# ELC102_-_Old_Circuits.net
KiCad netlist of a schematic drawn in Altium Designer
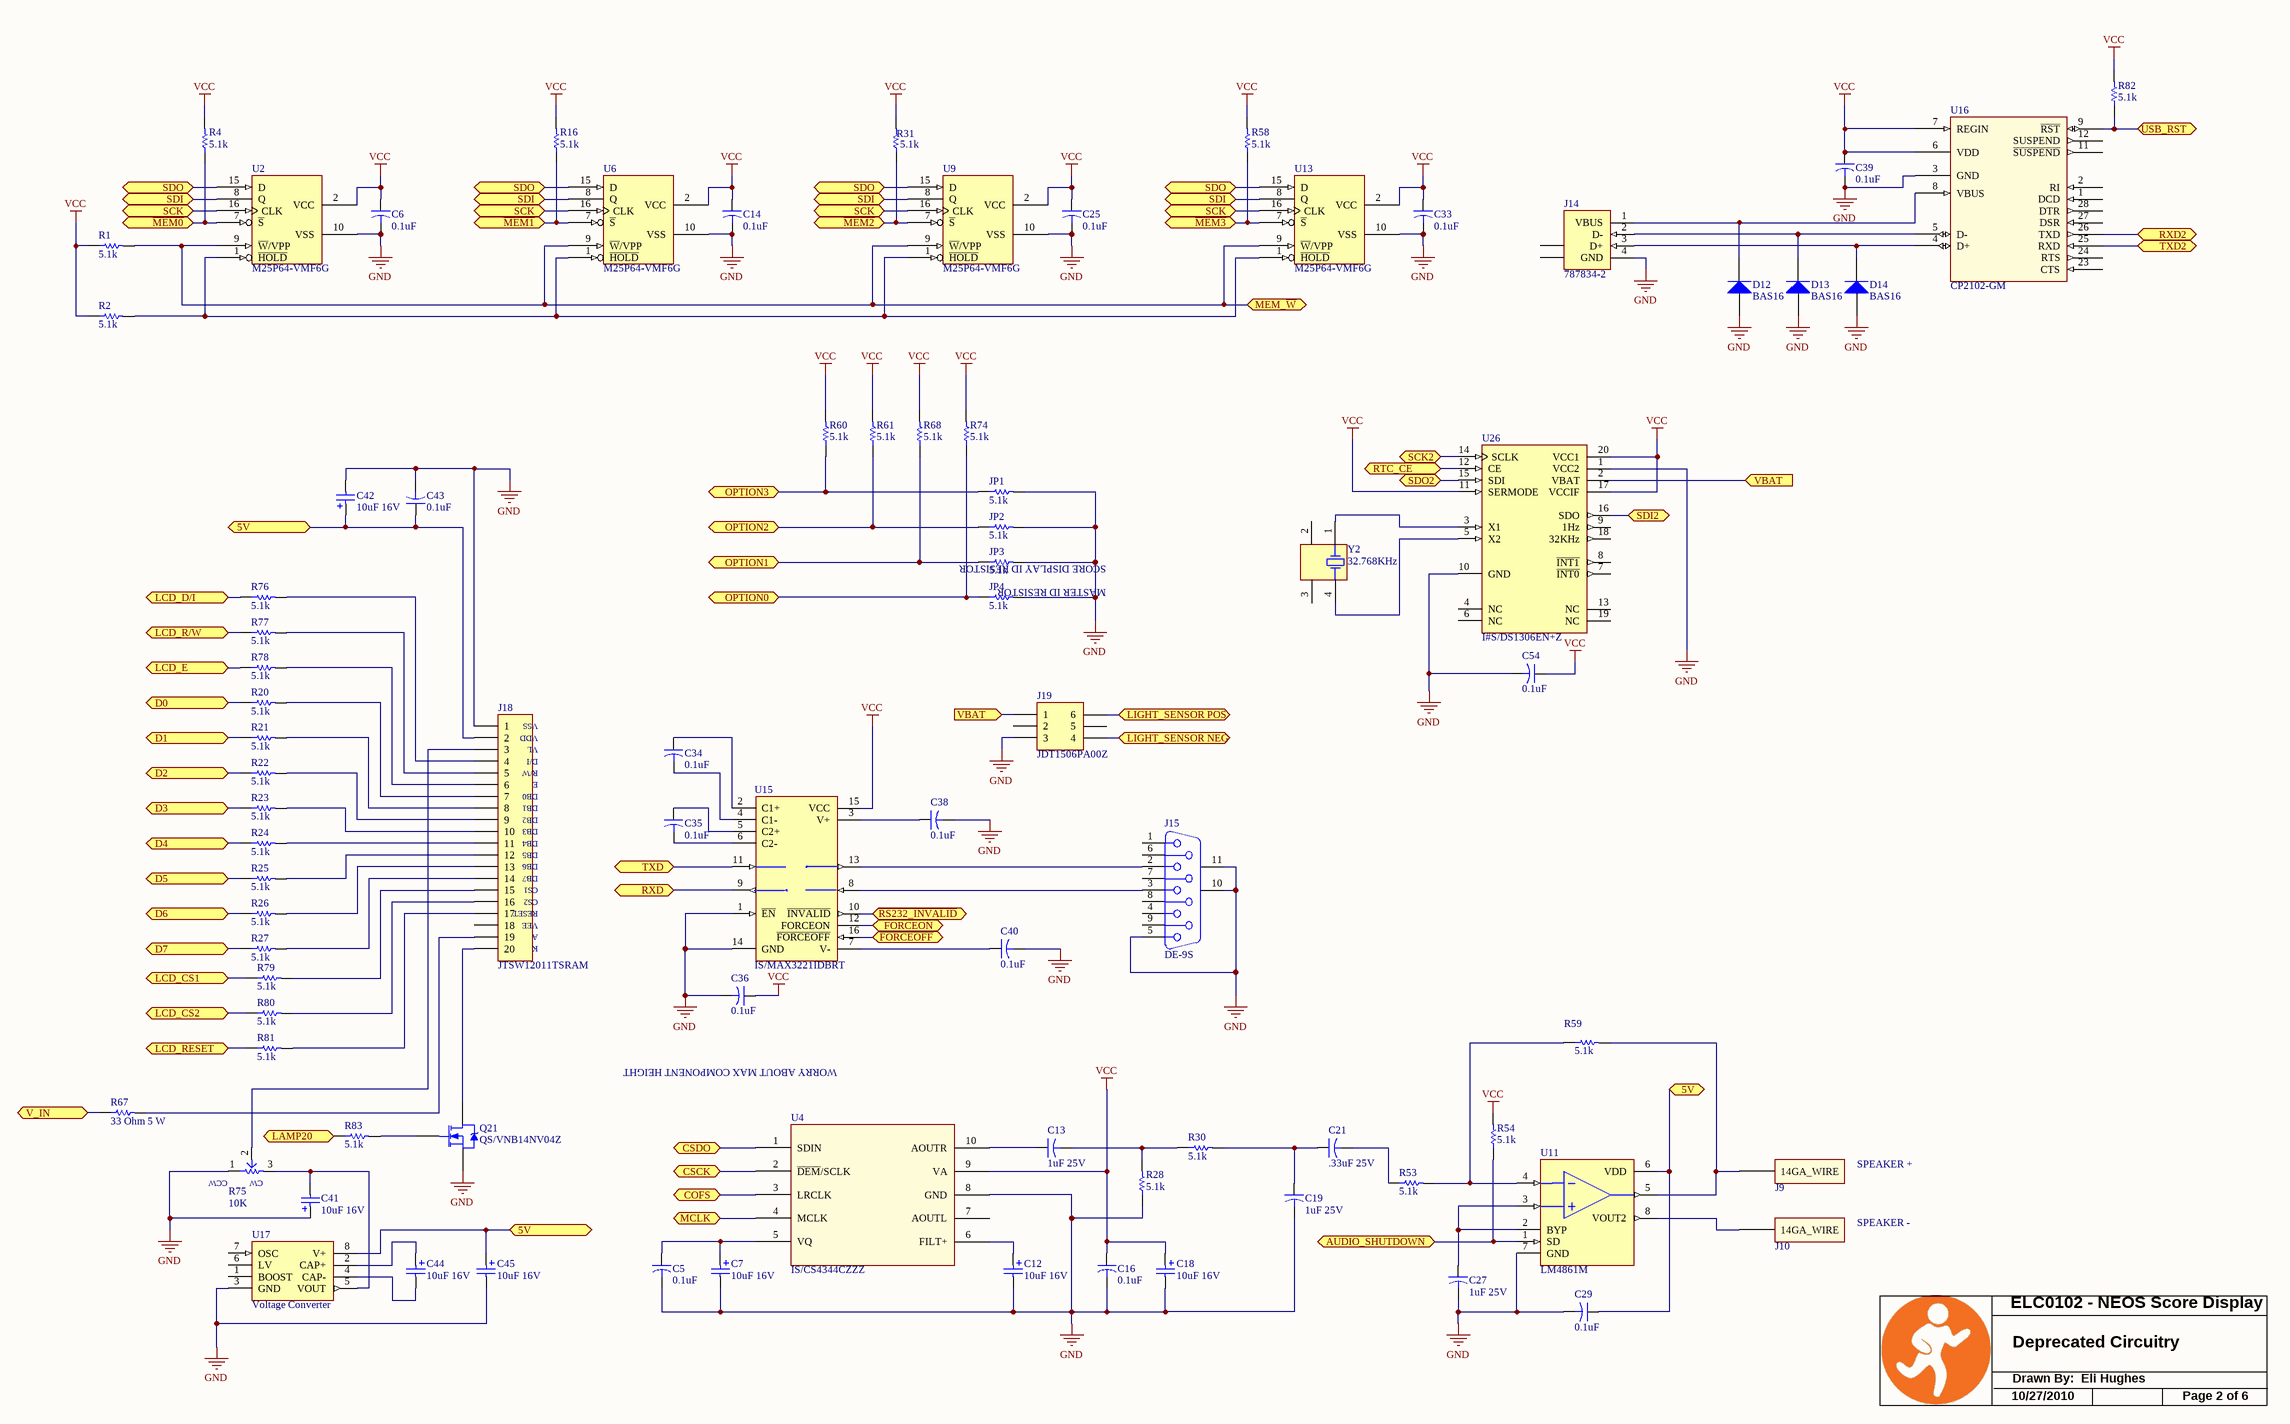
[diagram p0: ELC102 - Old Circuits.SchDoc]

(export (version "E")
  (design (tool "Eeschema 10.0.6"))
  (components
    (comp (ref "C5")
      (value "0.1uF")
      (footprint "C0805")
      (description "CAP .10UF 50V CERAMIC X7R 0805")
      (fields
        (field (name "MANUFACTURER") "Kemet")
        (field (name "MANUFACTURER PART NUMBER") "C0805C104K5RACTU")
        (field (name "SOURCE") "Digikey")
      )
      (libsource (lib "ELC102 - Scoreboard") (part "CS/C0805C104K5RACK"))
    )
    (comp (ref "C6")
      (value "0.1uF")
      (footprint "C0805")
      (description "CAP .10UF 50V CERAMIC X7R 0805")
      (fields
        (field (name "MANUFACTURER") "Kemet")
        (field (name "MANUFACTURER PART NUMBER") "C0805C104K5RACTU")
        (field (name "SOURCE") "Digikey")
      )
      (libsource (lib "ELC102 - Scoreboard") (part "CS/C0805C104K5RACK"))
    )
    (comp (ref "C7")
      (value "10uF 16V")
      (footprint "C4X5.8")
      (description "Panasonic 10uF 16V SMT")
      (fields
        (field (name "MANUFACTURER") "Panasonic - ECG")
        (field (name "MANUFACTURER PART NUMBER") "EEE-FK1C100R")
        (field (name "SOURCE") "Digikey")
      )
      (libsource (lib "ScoreBoard") (part "CS/EEVFK1C100RP"))
    )
    (comp (ref "C12")
      (value "10uF 16V")
      (footprint "C4X5.8")
      (description "Panasonic 10uF 16V SMT")
      (fields
        (field (name "MANUFACTURER") "Panasonic - ECG")
        (field (name "MANUFACTURER PART NUMBER") "EEE-FK1C100R")
        (field (name "SOURCE") "Digikey")
      )
      (libsource (lib "ScoreBoard") (part "CS/EEVFK1C100RP"))
    )
    (comp (ref "C13")
      (value "1uF 25V")
      (footprint "R1206")
      (description "1uF 25V 1206 Panasonic")
      (fields
        (field (name "MANUFACTURER") "Panasonic - ECG")
        (field (name "MANUFACTURER PART NUMBER") "ECJ-3YB1E105K")
        (field (name "PUBLISHER") "Altium Limited")
      )
      (libsource (lib "ScoreBoard") (part "CS/ECJ3YB1E105KP"))
    )
    (comp (ref "C14")
      (value "0.1uF")
      (footprint "C0805")
      (description "CAP .10UF 50V CERAMIC X7R 0805")
      (fields
        (field (name "MANUFACTURER") "Kemet")
        (field (name "MANUFACTURER PART NUMBER") "C0805C104K5RACTU")
        (field (name "SOURCE") "Digikey")
      )
      (libsource (lib "ELC102 - Scoreboard") (part "CS/C0805C104K5RACK"))
    )
    (comp (ref "C16")
      (value "0.1uF")
      (footprint "C0805")
      (description "CAP .10UF 50V CERAMIC X7R 0805")
      (fields
        (field (name "MANUFACTURER") "Kemet")
        (field (name "MANUFACTURER PART NUMBER") "C0805C104K5RACTU")
        (field (name "SOURCE") "Digikey")
      )
      (libsource (lib "ELC102 - Scoreboard") (part "CS/C0805C104K5RACK"))
    )
    (comp (ref "C18")
      (value "10uF 16V")
      (footprint "C4X5.8")
      (description "Panasonic 10uF 16V SMT")
      (fields
        (field (name "MANUFACTURER") "Panasonic - ECG")
        (field (name "MANUFACTURER PART NUMBER") "EEE-FK1C100R")
        (field (name "SOURCE") "Digikey")
      )
      (libsource (lib "ScoreBoard") (part "CS/EEVFK1C100RP"))
    )
    (comp (ref "C19")
      (value "1uF 25V")
      (footprint "R1206")
      (description "1uF 25V 1206 Panasonic")
      (fields
        (field (name "MANUFACTURER") "Panasonic - ECG")
        (field (name "MANUFACTURER PART NUMBER") "ECJ-3YB1E105K")
        (field (name "PUBLISHER") "Altium Limited")
      )
      (libsource (lib "ScoreBoard") (part "CS/ECJ3YB1E105KP"))
    )
    (comp (ref "C21")
      (value ".33uF 25V")
      (footprint "R1206")
      (description ".33uF 25V 1206 Panasonic")
      (fields
        (field (name "MANUFACTURER") "Panasonic - ECG")
        (field (name "MANUFACTURER PART NUMBER") "ECJ-3VB1E334K")
        (field (name "PUBLISHER") "Altium Limited")
      )
      (libsource (lib "ScoreBoard") (part "CS/ECJ3VB1E334KP"))
    )
    (comp (ref "C25")
      (value "0.1uF")
      (footprint "C0805")
      (description "CAP .10UF 50V CERAMIC X7R 0805")
      (fields
        (field (name "MANUFACTURER") "Kemet")
        (field (name "MANUFACTURER PART NUMBER") "C0805C104K5RACTU")
        (field (name "SOURCE") "Digikey")
      )
      (libsource (lib "ELC102 - Scoreboard") (part "CS/C0805C104K5RACK"))
    )
    (comp (ref "C27")
      (value "1uF 25V")
      (footprint "R1206")
      (description "1uF 25V 1206 Panasonic")
      (fields
        (field (name "MANUFACTURER") "Panasonic - ECG")
        (field (name "MANUFACTURER PART NUMBER") "ECJ-3YB1E105K")
        (field (name "PUBLISHER") "Altium Limited")
      )
      (libsource (lib "ScoreBoard") (part "CS/ECJ3YB1E105KP"))
    )
    (comp (ref "C29")
      (value "0.1uF")
      (footprint "C0805")
      (description "CAP .10UF 50V CERAMIC X7R 0805")
      (fields
        (field (name "MANUFACTURER") "Kemet")
        (field (name "MANUFACTURER PART NUMBER") "C0805C104K5RACTU")
        (field (name "SOURCE") "Digikey")
      )
      (libsource (lib "ELC102 - Scoreboard") (part "CS/C0805C104K5RACK"))
    )
    (comp (ref "C33")
      (value "0.1uF")
      (footprint "C0805")
      (description "CAP .10UF 50V CERAMIC X7R 0805")
      (fields
        (field (name "MANUFACTURER") "Kemet")
        (field (name "MANUFACTURER PART NUMBER") "C0805C104K5RACTU")
        (field (name "SOURCE") "Digikey")
      )
      (libsource (lib "ELC102 - Scoreboard") (part "CS/C0805C104K5RACK"))
    )
    (comp (ref "C34")
      (value "0.1uF")
      (footprint "C0805")
      (description "CAP .10UF 50V CERAMIC X7R 0805")
      (fields
        (field (name "MANUFACTURER") "Kemet")
        (field (name "MANUFACTURER PART NUMBER") "C0805C104K5RACTU")
        (field (name "SOURCE") "Digikey")
      )
      (libsource (lib "ELC102 - Scoreboard") (part "CS/C0805C104K5RACK"))
    )
    (comp (ref "C35")
      (value "0.1uF")
      (footprint "C0805")
      (description "CAP .10UF 50V CERAMIC X7R 0805")
      (fields
        (field (name "MANUFACTURER") "Kemet")
        (field (name "MANUFACTURER PART NUMBER") "C0805C104K5RACTU")
        (field (name "SOURCE") "Digikey")
      )
      (libsource (lib "ELC102 - Scoreboard") (part "CS/C0805C104K5RACK"))
    )
    (comp (ref "C36")
      (value "0.1uF")
      (footprint "C0805")
      (description "CAP .10UF 50V CERAMIC X7R 0805")
      (fields
        (field (name "MANUFACTURER") "Kemet")
        (field (name "MANUFACTURER PART NUMBER") "C0805C104K5RACTU")
        (field (name "SOURCE") "Digikey")
      )
      (libsource (lib "ELC102 - Scoreboard") (part "CS/C0805C104K5RACK"))
    )
    (comp (ref "C38")
      (value "0.1uF")
      (footprint "C0805")
      (description "CAP .10UF 50V CERAMIC X7R 0805")
      (fields
        (field (name "MANUFACTURER") "Kemet")
        (field (name "MANUFACTURER PART NUMBER") "C0805C104K5RACTU")
        (field (name "SOURCE") "Digikey")
      )
      (libsource (lib "ELC102 - Scoreboard") (part "CS/C0805C104K5RACK"))
    )
    (comp (ref "C39")
      (value "0.1uF")
      (footprint "C0805")
      (description "CAP .10UF 50V CERAMIC X7R 0805")
      (fields
        (field (name "MANUFACTURER") "Kemet")
        (field (name "MANUFACTURER PART NUMBER") "C0805C104K5RACTU")
        (field (name "SOURCE") "Digikey")
      )
      (libsource (lib "ELC102 - Scoreboard") (part "CS/C0805C104K5RACK"))
    )
    (comp (ref "C40")
      (value "0.1uF")
      (footprint "C0805")
      (description "CAP .10UF 50V CERAMIC X7R 0805")
      (fields
        (field (name "MANUFACTURER") "Kemet")
        (field (name "MANUFACTURER PART NUMBER") "C0805C104K5RACTU")
        (field (name "SOURCE") "Digikey")
      )
      (libsource (lib "ELC102 - Scoreboard") (part "CS/C0805C104K5RACK"))
    )
    (comp (ref "C41")
      (value "10uF 16V")
      (footprint "C4X5.8")
      (description "Panasonic 10uF 16V SMT")
      (fields
        (field (name "MANUFACTURER") "Panasonic - ECG")
        (field (name "MANUFACTURER PART NUMBER") "EEE-FK1C100R")
        (field (name "SOURCE") "Digikey")
      )
      (libsource (lib "ScoreBoard") (part "CS/EEVFK1C100RP"))
    )
    (comp (ref "C42")
      (value "10uF 16V")
      (footprint "C4X5.8")
      (description "Panasonic 10uF 16V SMT")
      (fields
        (field (name "MANUFACTURER") "Panasonic - ECG")
        (field (name "MANUFACTURER PART NUMBER") "EEE-FK1C100R")
        (field (name "SOURCE") "Digikey")
      )
      (libsource (lib "ScoreBoard") (part "CS/EEVFK1C100RP"))
    )
    (comp (ref "C43")
      (value "0.1uF")
      (footprint "C0805")
      (description "CAP .10UF 50V CERAMIC X7R 0805")
      (fields
        (field (name "MANUFACTURER") "Kemet")
        (field (name "MANUFACTURER PART NUMBER") "C0805C104K5RACTU")
        (field (name "SOURCE") "Digikey")
      )
      (libsource (lib "ELC102 - Scoreboard") (part "CS/C0805C104K5RACK"))
    )
    (comp (ref "C44")
      (value "10uF 16V")
      (footprint "C4X5.8")
      (description "Panasonic 10uF 16V SMT")
      (fields
        (field (name "MANUFACTURER") "Panasonic - ECG")
        (field (name "MANUFACTURER PART NUMBER") "EEE-FK1C100R")
        (field (name "SOURCE") "Digikey")
      )
      (libsource (lib "ScoreBoard") (part "CS/EEVFK1C100RP"))
    )
    (comp (ref "C45")
      (value "10uF 16V")
      (footprint "C4X5.8")
      (description "Panasonic 10uF 16V SMT")
      (fields
        (field (name "MANUFACTURER") "Panasonic - ECG")
        (field (name "MANUFACTURER PART NUMBER") "EEE-FK1C100R")
        (field (name "SOURCE") "Digikey")
      )
      (libsource (lib "ScoreBoard") (part "CS/EEVFK1C100RP"))
    )
    (comp (ref "C54")
      (value "0.1uF")
      (footprint "C0805")
      (description "CAP .10UF 50V CERAMIC X7R 0805")
      (fields
        (field (name "MANUFACTURER") "Kemet")
        (field (name "MANUFACTURER PART NUMBER") "C0805C104K5RACTU")
        (field (name "SOURCE") "Digikey")
      )
      (libsource (lib "ELC102 - Scoreboard") (part "CS/C0805C104K5RACK"))
    )
    (comp (ref "D12")
      (value "BAS16")
      (footprint "SOT23")
      (description "Zetex BAS16 Diode")
      (fields
        (field (name "MANUFACTURER") "Diodes Inc")
        (field (name "MANUFACTURER PART NUMBER") "BAS16-7-F")
        (field (name "PUBLISHER") "Altium Limited")
      )
      (libsource (lib "ScoreBoard") (part "DS/BAS16000Z"))
    )
    (comp (ref "D13")
      (value "BAS16")
      (footprint "SOT23")
      (description "Zetex BAS16 Diode")
      (fields
        (field (name "MANUFACTURER") "Diodes Inc")
        (field (name "MANUFACTURER PART NUMBER") "BAS16-7-F")
        (field (name "PUBLISHER") "Altium Limited")
      )
      (libsource (lib "ScoreBoard") (part "DS/BAS16000Z"))
    )
    (comp (ref "D14")
      (value "BAS16")
      (footprint "SOT23")
      (description "Zetex BAS16 Diode")
      (fields
        (field (name "MANUFACTURER") "Diodes Inc")
        (field (name "MANUFACTURER PART NUMBER") "BAS16-7-F")
        (field (name "PUBLISHER") "Altium Limited")
      )
      (libsource (lib "ScoreBoard") (part "DS/BAS16000Z"))
    )
    (comp (ref "J9")
      (value "~14GA_WIRE")
      (footprint "WIRE_14GA")
      (libsource (lib "ScoreBoard") (part "~14GA_WIRE"))
    )
    (comp (ref "J10")
      (value "~14GA_WIRE")
      (footprint "WIRE_14GA")
      (libsource (lib "ScoreBoard") (part "~14GA_WIRE"))
    )
    (comp (ref "J14")
      (value "787834-2")
      (footprint "KUSBVX-BS1N")
      (description "USB 1.1, Vertical, Thru-Hole, B Type, Receptacle, 4 Position, Natural")
      (fields
        (field (name "MANUFACTURER") "Tyco Electronics")
        (field (name "MANUFACTURER PART NUMBER") "5787834-2")
        (field (name "PUBLISHER") "Altium Limited")
      )
      (libsource (lib "ScoreBoard") (part "787834-2"))
    )
    (comp (ref "J15")
      (value "DE-9S")
      (footprint "DSUBV9")
      (description "D-Sub 9S Kycon Straight W/retainers")
      (fields (field (name "PUBLISHER") "Altium Limited"))
      (libsource (lib "ScoreBoard") (part "JK85ED9SBR0Z"))
    )
    (comp (ref "J18")
      (value "JTSW12011TSRAM")
      (footprint "JTSW12011TSRAM")
      (description "Samtec Header RA 20P Stood off board")
      (fields (field (name "PUBLISHER") "Altium Limited"))
      (libsource (lib "ScoreBoard") (part "JTSW12011TSRAM"))
    )
    (comp (ref "J19")
      (value "JDT1506PA00Z")
      (footprint "JDT1506PA00Z - 2 holes")
      (description "Deutsch 6P Sealed PCB connector")
      (libsource (lib "ScoreBoard") (part "JDT1506PA00Z"))
    )
    (comp (ref "JP1")
      (value "5.1k")
      (footprint "R0805")
      (description "RES 5.10K OHM 1/8W 1% 0805 SMD")
      (fields
        (field (name "MANUFACTURER") "Panasonic - ECG")
        (field (name "MANUFACTURER PART NUMBER") "ERJ-6ENF5101V")
      )
      (libsource (lib "eRCL") (part "ERJ-6ENF5101V"))
    )
    (comp (ref "JP2")
      (value "5.1k")
      (footprint "R0805")
      (description "RES 5.10K OHM 1/8W 1% 0805 SMD")
      (fields
        (field (name "MANUFACTURER") "Panasonic - ECG")
        (field (name "MANUFACTURER PART NUMBER") "ERJ-6ENF5101V")
      )
      (libsource (lib "eRCL") (part "ERJ-6ENF5101V"))
    )
    (comp (ref "JP3")
      (value "5.1k")
      (footprint "R0805")
      (description "RES 5.10K OHM 1/8W 1% 0805 SMD")
      (fields
        (field (name "MANUFACTURER") "Panasonic - ECG")
        (field (name "MANUFACTURER PART NUMBER") "ERJ-6ENF5101V")
      )
      (libsource (lib "eRCL") (part "ERJ-6ENF5101V"))
    )
    (comp (ref "JP4")
      (value "5.1k")
      (footprint "R0805")
      (description "RES 5.10K OHM 1/8W 1% 0805 SMD")
      (fields
        (field (name "MANUFACTURER") "Panasonic - ECG")
        (field (name "MANUFACTURER PART NUMBER") "ERJ-6ENF5101V")
      )
      (libsource (lib "eRCL") (part "ERJ-6ENF5101V"))
    )
    (comp (ref "Q21")
      (value "QS/VNB14NV04Z")
      (footprint "D2PAK")
      (description "HEXFET Power MOSFET")
      (fields
        (field (name "MANUFACTURER") "STMicroelectronics")
        (field (name "MANUFACTURER PART NUMBER") "VNB14NV04")
        (field (name "SOURCE") "Digikey")
      )
      (libsource (lib "ScoreBoard") (part "QS/VNB14NV04Z"))
    )
    (comp (ref "R1")
      (value "5.1k")
      (footprint "R0805")
      (description "RES 5.10K OHM 1/8W 1% 0805 SMD")
      (fields
        (field (name "MANUFACTURER") "Panasonic - ECG")
        (field (name "MANUFACTURER PART NUMBER") "ERJ-6ENF5101V")
      )
      (libsource (lib "eRCL") (part "ERJ-6ENF5101V"))
    )
    (comp (ref "R2")
      (value "5.1k")
      (footprint "R0805")
      (description "RES 5.10K OHM 1/8W 1% 0805 SMD")
      (fields
        (field (name "MANUFACTURER") "Panasonic - ECG")
        (field (name "MANUFACTURER PART NUMBER") "ERJ-6ENF5101V")
      )
      (libsource (lib "eRCL") (part "ERJ-6ENF5101V"))
    )
    (comp (ref "R4")
      (value "5.1k")
      (footprint "R0805")
      (description "RES 5.10K OHM 1/8W 1% 0805 SMD")
      (fields
        (field (name "MANUFACTURER") "Panasonic - ECG")
        (field (name "MANUFACTURER PART NUMBER") "ERJ-6ENF5101V")
      )
      (libsource (lib "eRCL") (part "ERJ-6ENF5101V"))
    )
    (comp (ref "R16")
      (value "5.1k")
      (footprint "R0805")
      (description "RES 5.10K OHM 1/8W 1% 0805 SMD")
      (fields
        (field (name "MANUFACTURER") "Panasonic - ECG")
        (field (name "MANUFACTURER PART NUMBER") "ERJ-6ENF5101V")
      )
      (libsource (lib "eRCL") (part "ERJ-6ENF5101V"))
    )
    (comp (ref "R20")
      (value "5.1k")
      (footprint "R0805")
      (description "RES 5.10K OHM 1/8W 1% 0805 SMD")
      (fields
        (field (name "MANUFACTURER") "Panasonic - ECG")
        (field (name "MANUFACTURER PART NUMBER") "ERJ-6ENF5101V")
      )
      (libsource (lib "eRCL") (part "ERJ-6ENF5101V"))
    )
    (comp (ref "R21")
      (value "5.1k")
      (footprint "R0805")
      (description "RES 5.10K OHM 1/8W 1% 0805 SMD")
      (fields
        (field (name "MANUFACTURER") "Panasonic - ECG")
        (field (name "MANUFACTURER PART NUMBER") "ERJ-6ENF5101V")
      )
      (libsource (lib "eRCL") (part "ERJ-6ENF5101V"))
    )
    (comp (ref "R22")
      (value "5.1k")
      (footprint "R0805")
      (description "RES 5.10K OHM 1/8W 1% 0805 SMD")
      (fields
        (field (name "MANUFACTURER") "Panasonic - ECG")
        (field (name "MANUFACTURER PART NUMBER") "ERJ-6ENF5101V")
      )
      (libsource (lib "eRCL") (part "ERJ-6ENF5101V"))
    )
    (comp (ref "R23")
      (value "5.1k")
      (footprint "R0805")
      (description "RES 5.10K OHM 1/8W 1% 0805 SMD")
      (fields
        (field (name "MANUFACTURER") "Panasonic - ECG")
        (field (name "MANUFACTURER PART NUMBER") "ERJ-6ENF5101V")
      )
      (libsource (lib "eRCL") (part "ERJ-6ENF5101V"))
    )
    (comp (ref "R24")
      (value "5.1k")
      (footprint "R0805")
      (description "RES 5.10K OHM 1/8W 1% 0805 SMD")
      (fields
        (field (name "MANUFACTURER") "Panasonic - ECG")
        (field (name "MANUFACTURER PART NUMBER") "ERJ-6ENF5101V")
      )
      (libsource (lib "eRCL") (part "ERJ-6ENF5101V"))
    )
    (comp (ref "R25")
      (value "5.1k")
      (footprint "R0805")
      (description "RES 5.10K OHM 1/8W 1% 0805 SMD")
      (fields
        (field (name "MANUFACTURER") "Panasonic - ECG")
        (field (name "MANUFACTURER PART NUMBER") "ERJ-6ENF5101V")
      )
      (libsource (lib "eRCL") (part "ERJ-6ENF5101V"))
    )
    (comp (ref "R26")
      (value "5.1k")
      (footprint "R0805")
      (description "RES 5.10K OHM 1/8W 1% 0805 SMD")
      (fields
        (field (name "MANUFACTURER") "Panasonic - ECG")
        (field (name "MANUFACTURER PART NUMBER") "ERJ-6ENF5101V")
      )
      (libsource (lib "eRCL") (part "ERJ-6ENF5101V"))
    )
    (comp (ref "R27")
      (value "5.1k")
      (footprint "R0805")
      (description "RES 5.10K OHM 1/8W 1% 0805 SMD")
      (fields
        (field (name "MANUFACTURER") "Panasonic - ECG")
        (field (name "MANUFACTURER PART NUMBER") "ERJ-6ENF5101V")
      )
      (libsource (lib "eRCL") (part "ERJ-6ENF5101V"))
    )
    (comp (ref "R28")
      (value "5.1k")
      (footprint "R0805")
      (description "RES 5.10K OHM 1/8W 1% 0805 SMD")
      (fields
        (field (name "MANUFACTURER") "Panasonic - ECG")
        (field (name "MANUFACTURER PART NUMBER") "ERJ-6ENF5101V")
      )
      (libsource (lib "eRCL") (part "ERJ-6ENF5101V"))
    )
    (comp (ref "R30")
      (value "5.1k")
      (footprint "R0805")
      (description "RES 5.10K OHM 1/8W 1% 0805 SMD")
      (fields
        (field (name "MANUFACTURER") "Panasonic - ECG")
        (field (name "MANUFACTURER PART NUMBER") "ERJ-6ENF5101V")
      )
      (libsource (lib "eRCL") (part "ERJ-6ENF5101V"))
    )
    (comp (ref "R31")
      (value "5.1k")
      (footprint "R0805")
      (description "RES 5.10K OHM 1/8W 1% 0805 SMD")
      (fields
        (field (name "MANUFACTURER") "Panasonic - ECG")
        (field (name "MANUFACTURER PART NUMBER") "ERJ-6ENF5101V")
      )
      (libsource (lib "eRCL") (part "ERJ-6ENF5101V"))
    )
    (comp (ref "R53")
      (value "5.1k")
      (footprint "R0805")
      (description "RES 5.10K OHM 1/8W 1% 0805 SMD")
      (fields
        (field (name "MANUFACTURER") "Panasonic - ECG")
        (field (name "MANUFACTURER PART NUMBER") "ERJ-6ENF5101V")
      )
      (libsource (lib "eRCL") (part "ERJ-6ENF5101V"))
    )
    (comp (ref "R54")
      (value "5.1k")
      (footprint "R0805")
      (description "RES 5.10K OHM 1/8W 1% 0805 SMD")
      (fields
        (field (name "MANUFACTURER") "Panasonic - ECG")
        (field (name "MANUFACTURER PART NUMBER") "ERJ-6ENF5101V")
      )
      (libsource (lib "eRCL") (part "ERJ-6ENF5101V"))
    )
    (comp (ref "R58")
      (value "5.1k")
      (footprint "R0805")
      (description "RES 5.10K OHM 1/8W 1% 0805 SMD")
      (fields
        (field (name "MANUFACTURER") "Panasonic - ECG")
        (field (name "MANUFACTURER PART NUMBER") "ERJ-6ENF5101V")
      )
      (libsource (lib "eRCL") (part "ERJ-6ENF5101V"))
    )
    (comp (ref "R59")
      (value "5.1k")
      (footprint "R0805")
      (description "RES 5.10K OHM 1/8W 1% 0805 SMD")
      (fields
        (field (name "MANUFACTURER") "Panasonic - ECG")
        (field (name "MANUFACTURER PART NUMBER") "ERJ-6ENF5101V")
      )
      (libsource (lib "eRCL") (part "ERJ-6ENF5101V"))
    )
    (comp (ref "R60")
      (value "5.1k")
      (footprint "R0805")
      (description "RES 5.10K OHM 1/8W 1% 0805 SMD")
      (fields
        (field (name "MANUFACTURER") "Panasonic - ECG")
        (field (name "MANUFACTURER PART NUMBER") "ERJ-6ENF5101V")
      )
      (libsource (lib "eRCL") (part "ERJ-6ENF5101V"))
    )
    (comp (ref "R61")
      (value "5.1k")
      (footprint "R0805")
      (description "RES 5.10K OHM 1/8W 1% 0805 SMD")
      (fields
        (field (name "MANUFACTURER") "Panasonic - ECG")
        (field (name "MANUFACTURER PART NUMBER") "ERJ-6ENF5101V")
      )
      (libsource (lib "eRCL") (part "ERJ-6ENF5101V"))
    )
    (comp (ref "R67")
      (value "33 Ohm 5 W")
      (footprint "RES30.6-25.5X9")
      (description "Resistor 5W square ceramic")
      (fields (field (name "PUBLISHER") "Altium Limited"))
      (libsource (lib "ScoreBoard") (part "RES 5W"))
    )
    (comp (ref "R68")
      (value "5.1k")
      (footprint "R0805")
      (description "RES 5.10K OHM 1/8W 1% 0805 SMD")
      (fields
        (field (name "MANUFACTURER") "Panasonic - ECG")
        (field (name "MANUFACTURER PART NUMBER") "ERJ-6ENF5101V")
      )
      (libsource (lib "eRCL") (part "ERJ-6ENF5101V"))
    )
    (comp (ref "R74")
      (value "5.1k")
      (footprint "R0805")
      (description "RES 5.10K OHM 1/8W 1% 0805 SMD")
      (fields
        (field (name "MANUFACTURER") "Panasonic - ECG")
        (field (name "MANUFACTURER PART NUMBER") "ERJ-6ENF5101V")
      )
      (libsource (lib "eRCL") (part "ERJ-6ENF5101V"))
    )
    (comp (ref "R75")
      (value "10K")
      (footprint "P3299W")
      (description "Bourns Trim Pot 10K Vertical")
      (fields (field (name "PUBLISHER") "Altium Limited"))
      (libsource (lib "ScoreBoard") (part "P3299W11030B"))
    )
    (comp (ref "R76")
      (value "5.1k")
      (footprint "R0805")
      (description "RES 5.10K OHM 1/8W 1% 0805 SMD")
      (fields
        (field (name "MANUFACTURER") "Panasonic - ECG")
        (field (name "MANUFACTURER PART NUMBER") "ERJ-6ENF5101V")
      )
      (libsource (lib "eRCL") (part "ERJ-6ENF5101V"))
    )
    (comp (ref "R77")
      (value "5.1k")
      (footprint "R0805")
      (description "RES 5.10K OHM 1/8W 1% 0805 SMD")
      (fields
        (field (name "MANUFACTURER") "Panasonic - ECG")
        (field (name "MANUFACTURER PART NUMBER") "ERJ-6ENF5101V")
      )
      (libsource (lib "eRCL") (part "ERJ-6ENF5101V"))
    )
    (comp (ref "R78")
      (value "5.1k")
      (footprint "R0805")
      (description "RES 5.10K OHM 1/8W 1% 0805 SMD")
      (fields
        (field (name "MANUFACTURER") "Panasonic - ECG")
        (field (name "MANUFACTURER PART NUMBER") "ERJ-6ENF5101V")
      )
      (libsource (lib "eRCL") (part "ERJ-6ENF5101V"))
    )
    (comp (ref "R79")
      (value "5.1k")
      (footprint "R0805")
      (description "RES 5.10K OHM 1/8W 1% 0805 SMD")
      (fields
        (field (name "MANUFACTURER") "Panasonic - ECG")
        (field (name "MANUFACTURER PART NUMBER") "ERJ-6ENF5101V")
      )
      (libsource (lib "eRCL") (part "ERJ-6ENF5101V"))
    )
    (comp (ref "R80")
      (value "5.1k")
      (footprint "R0805")
      (description "RES 5.10K OHM 1/8W 1% 0805 SMD")
      (fields
        (field (name "MANUFACTURER") "Panasonic - ECG")
        (field (name "MANUFACTURER PART NUMBER") "ERJ-6ENF5101V")
      )
      (libsource (lib "eRCL") (part "ERJ-6ENF5101V"))
    )
    (comp (ref "R81")
      (value "5.1k")
      (footprint "R0805")
      (description "RES 5.10K OHM 1/8W 1% 0805 SMD")
      (fields
        (field (name "MANUFACTURER") "Panasonic - ECG")
        (field (name "MANUFACTURER PART NUMBER") "ERJ-6ENF5101V")
      )
      (libsource (lib "eRCL") (part "ERJ-6ENF5101V"))
    )
    (comp (ref "R82")
      (value "5.1k")
      (footprint "R0805")
      (description "RES 5.10K OHM 1/8W 1% 0805 SMD")
      (fields
        (field (name "MANUFACTURER") "Panasonic - ECG")
        (field (name "MANUFACTURER PART NUMBER") "ERJ-6ENF5101V")
      )
      (libsource (lib "eRCL") (part "ERJ-6ENF5101V"))
    )
    (comp (ref "R83")
      (value "5.1k")
      (footprint "R0805")
      (description "RES 5.10K OHM 1/8W 1% 0805 SMD")
      (fields
        (field (name "MANUFACTURER") "Panasonic - ECG")
        (field (name "MANUFACTURER PART NUMBER") "ERJ-6ENF5101V")
      )
      (libsource (lib "eRCL") (part "ERJ-6ENF5101V"))
    )
    (comp (ref "U2")
      (value "M25P64-VMF6G")
      (footprint "so16w")
      (description "ST Serial memory 64MBit SOIC-16")
      (fields
        (field (name "MANUFACTURER") "NUMONYX")
        (field (name "MANUFACTURER PART NUMBER") "M25P64-VMF6P")
      )
      (libsource (lib "ScoreBoard") (part "IS/M25P64VMF6GZ"))
    )
    (comp (ref "U4")
      (value "IS/CS4344CZZZ")
      (footprint "TSSOP\\10")
      (description "Cirrus 24 bit DAC")
      (fields
        (field (name "MANUFACTURER") "Cirrus Logic Inc")
        (field (name "MANUFACTURER PART NUMBER") "CS4344-CZZR")
      )
      (libsource (lib "ScoreBoard") (part "IS/CS4344CZZZ"))
    )
    (comp (ref "U6")
      (value "M25P64-VMF6G")
      (footprint "so16w")
      (description "ST Serial memory 64MBit SOIC-16")
      (fields
        (field (name "MANUFACTURER") "NUMONYX")
        (field (name "MANUFACTURER PART NUMBER") "M25P64-VMF6P")
      )
      (libsource (lib "ScoreBoard") (part "IS/M25P64VMF6GZ"))
    )
    (comp (ref "U9")
      (value "M25P64-VMF6G")
      (footprint "so16w")
      (description "ST Serial memory 64MBit SOIC-16")
      (fields
        (field (name "MANUFACTURER") "NUMONYX")
        (field (name "MANUFACTURER PART NUMBER") "M25P64-VMF6P")
      )
      (libsource (lib "ScoreBoard") (part "IS/M25P64VMF6GZ"))
    )
    (comp (ref "U11")
      (value "LM4861M")
      (footprint "soic 8")
      (description "1.1 Audio Power Amplifier with Shutdown Mode")
      (fields
        (field (name "MANUFACTURER") "National Semiconductor")
        (field (name "MANUFACTURER PART NUMBER") "LM4861MX")
        (field (name "PUBLISHER") "Altium Limited")
      )
      (libsource (lib "ScoreBoard") (part "LM4861M"))
    )
    (comp (ref "U13")
      (value "M25P64-VMF6G")
      (footprint "so16w")
      (description "ST Serial memory 64MBit SOIC-16")
      (fields
        (field (name "MANUFACTURER") "NUMONYX")
        (field (name "MANUFACTURER PART NUMBER") "M25P64-VMF6P")
      )
      (libsource (lib "ScoreBoard") (part "IS/M25P64VMF6GZ"))
    )
    (comp (ref "U15")
      (value "IS/MAX3221IDBRT")
      (footprint "SSOP16")
      (description "TI 3.3V RS-232 chip 16-SSOP")
      (fields
        (field (name "MANUFACTURER") "Texas Instruments")
        (field (name "MANUFACTURER PART NUMBER") "MAX3221IDBR")
        (field (name "PUBLISHER") "Altium Limited")
      )
      (libsource (lib "ScoreBoard") (part "IS/MAX3221IDBRT"))
    )
    (comp (ref "U16")
      (value "CP2102-GM")
      (footprint "QFN28")
      (description "IC USB-TO-UART BRIDGE 28VQFN")
      (fields (field (name "MANUFACTURER") "Silicon Laboratories  Inc"))
      (libsource (lib "ScoreBoard") (part "IS/CP2102GMZ"))
    )
    (comp (ref "U17")
      (value "Voltage Converter")
      (footprint "SOIC 8")
      (description "Switched Capacitor Voltage Converter")
      (fields
        (field (name "MANUFACTURER") "Intersil")
        (field (name "MANUFACTURER PART NUMBER") "ICL7660ACBAZA-T")
        (field (name "PUBLISHER") "Altium Limited")
      )
      (libsource (lib "ScoreBoard") (part "IS/ICL7660ACBA"))
    )
    (comp (ref "U26")
      (value "I#S/DS1306EN+Z")
      (footprint "TSSOP-20")
      (description "Serial Alarm Real-Time Clock")
      (fields
        (field (name "MANUFACTURER") "Maxim Integrated Products")
        (field (name "MANUFACTURER PART NUMBER") "DS1306EN+")
        (field (name "PUBLISHER") "Altium Limited")
      )
      (libsource (lib "ScoreBoard") (part "I#S/DS1306EN+Z"))
    )
    (comp (ref "Y2")
      (value "32.768KHz")
      (footprint "ZS/MC306")
      (description "Epson MC-306 32.768K-E3")
      (fields (field (name "PUBLISHER") "Altium Limited"))
      (libsource (lib "ScoreBoard") (part "ZS/MC30632.768KE3Z"))
    )
  )
  (nets
    (net (code "1") (name "/5V") (class "Default")
      (node (ref "C29") (pin "1") (pinfunction "1_1") (pintype "passive"))
      (node (ref "C42") (pin "1") (pinfunction "1_1") (pintype "passive"))
      (node (ref "C43") (pin "1") (pinfunction "1_1") (pintype "passive"))
      (node (ref "C45") (pin "1") (pinfunction "1_1") (pintype "passive"))
      (node (ref "J18") (pin "2") (pinfunction "2_2") (pintype "passive"))
      (node (ref "U11") (pin "6") (pinfunction "VDD_6") (pintype "power_in"))
      (node (ref "U17") (pin "8") (pinfunction "V+_8") (pintype "power_in"))
    )
    (net (code "2") (name "/AUDIO_SHUTDOWN") (class "Default")
      (node (ref "R54") (pin "1") (pinfunction "1_1") (pintype "passive"))
      (node (ref "U11") (pin "1") (pinfunction "SD_1") (pintype "input"))
    )
    (net (code "3") (name "/COFS") (class "Default")
      (node (ref "U4") (pin "3") (pinfunction "LRCLK_3") (pintype "passive"))
    )
    (net (code "4") (name "/CSCK") (class "Default")
      (node (ref "U4") (pin "2") (pinfunction "~{DEM}/SCLK_2") (pintype "passive"))
    )
    (net (code "5") (name "/CSDO") (class "Default")
      (node (ref "U4") (pin "1") (pinfunction "SDIN_1") (pintype "passive"))
    )
    (net (code "6") (name "/D0") (class "Default")
      (node (ref "R20") (pin "1") (pinfunction "1_1") (pintype "passive"))
    )
    (net (code "7") (name "/D1") (class "Default")
      (node (ref "R21") (pin "1") (pinfunction "1_1") (pintype "passive"))
    )
    (net (code "8") (name "/D2") (class "Default")
      (node (ref "R22") (pin "1") (pinfunction "1_1") (pintype "passive"))
    )
    (net (code "9") (name "/D3") (class "Default")
      (node (ref "R23") (pin "1") (pinfunction "1_1") (pintype "passive"))
    )
    (net (code "10") (name "/D4") (class "Default")
      (node (ref "R24") (pin "1") (pinfunction "1_1") (pintype "passive"))
    )
    (net (code "11") (name "/D5") (class "Default")
      (node (ref "R25") (pin "1") (pinfunction "1_1") (pintype "passive"))
    )
    (net (code "12") (name "/D6") (class "Default")
      (node (ref "R26") (pin "1") (pinfunction "1_1") (pintype "passive"))
    )
    (net (code "13") (name "/D7") (class "Default")
      (node (ref "R27") (pin "1") (pinfunction "1_1") (pintype "passive"))
    )
    (net (code "14") (name "/FORCEON") (class "Default")
      (node (ref "U15") (pin "12") (pinfunction "FORCEON_12") (pintype "passive"))
    )
    (net (code "15") (name "/LAMP20") (class "Default")
      (node (ref "R83") (pin "1") (pinfunction "1_1") (pintype "passive"))
    )
    (net (code "16") (name "/LCD_CS1") (class "Default")
      (node (ref "R79") (pin "1") (pinfunction "1_1") (pintype "passive"))
    )
    (net (code "17") (name "/LCD_CS2") (class "Default")
      (node (ref "R80") (pin "1") (pinfunction "1_1") (pintype "passive"))
    )
    (net (code "18") (name "/LCD_D{slash}I") (class "Default")
      (node (ref "R76") (pin "1") (pinfunction "1_1") (pintype "passive"))
    )
    (net (code "19") (name "/LCD_E") (class "Default")
      (node (ref "R78") (pin "1") (pinfunction "1_1") (pintype "passive"))
    )
    (net (code "20") (name "/LCD_RESET") (class "Default")
      (node (ref "R81") (pin "1") (pinfunction "1_1") (pintype "passive"))
    )
    (net (code "21") (name "/LCD_R{slash}W") (class "Default")
      (node (ref "R77") (pin "1") (pinfunction "1_1") (pintype "passive"))
    )
    (net (code "22") (name "/LIGHT_SENSOR NEG") (class "Default")
      (node (ref "J19") (pin "4") (pinfunction "4_4") (pintype "passive"))
    )
    (net (code "23") (name "/LIGHT_SENSOR POS") (class "Default")
      (node (ref "J19") (pin "6") (pinfunction "6_6") (pintype "passive"))
    )
    (net (code "24") (name "/MCLK") (class "Default")
      (node (ref "U4") (pin "4") (pinfunction "MCLK_4") (pintype "passive"))
    )
    (net (code "25") (name "/MEM_~{W}") (class "Default")
      (node (ref "R1") (pin "2") (pinfunction "2_2") (pintype "passive"))
      (node (ref "U13") (pin "9") (pinfunction "~{W}/VPP_9") (pintype "input"))
      (node (ref "U2") (pin "9") (pinfunction "~{W}/VPP_9") (pintype "input"))
      (node (ref "U6") (pin "9") (pinfunction "~{W}/VPP_9") (pintype "input"))
      (node (ref "U9") (pin "9") (pinfunction "~{W}/VPP_9") (pintype "input"))
    )
    (net (code "26") (name "/OPTION0") (class "Default")
      (node (ref "JP4") (pin "1") (pinfunction "1_1") (pintype "passive"))
      (node (ref "R74") (pin "1") (pinfunction "1_1") (pintype "passive"))
    )
    (net (code "27") (name "/OPTION1") (class "Default")
      (node (ref "JP3") (pin "1") (pinfunction "1_1") (pintype "passive"))
      (node (ref "R68") (pin "1") (pinfunction "1_1") (pintype "passive"))
    )
    (net (code "28") (name "/OPTION2") (class "Default")
      (node (ref "JP2") (pin "1") (pinfunction "1_1") (pintype "passive"))
      (node (ref "R61") (pin "1") (pinfunction "1_1") (pintype "passive"))
    )
    (net (code "29") (name "/OPTION3") (class "Default")
      (node (ref "JP1") (pin "1") (pinfunction "1_1") (pintype "passive"))
      (node (ref "R60") (pin "1") (pinfunction "1_1") (pintype "passive"))
    )
    (net (code "30") (name "/RTC_CE") (class "Default")
      (node (ref "U26") (pin "12") (pinfunction "CE_12") (pintype "input"))
    )
    (net (code "31") (name "/RXD") (class "Default")
      (node (ref "U15") (pin "9") (pinfunction "R1OUT_9") (pintype "output"))
    )
    (net (code "32") (name "/RXD2") (class "Default")
      (node (ref "U16") (pin "26") (pinfunction "TXD_26") (pintype "output"))
    )
    (net (code "33") (name "/SCK") (class "Default")
      (node (ref "U13") (pin "16") (pinfunction "CLK_16") (pintype "input"))
      (node (ref "U2") (pin "16") (pinfunction "CLK_16") (pintype "input"))
      (node (ref "U6") (pin "16") (pinfunction "CLK_16") (pintype "input"))
      (node (ref "U9") (pin "16") (pinfunction "CLK_16") (pintype "input"))
    )
    (net (code "34") (name "/SCK2") (class "Default")
      (node (ref "U26") (pin "14") (pinfunction "SCLK_14") (pintype "input"))
    )
    (net (code "35") (name "/SDI") (class "Default")
      (node (ref "U13") (pin "8") (pinfunction "Q_8") (pintype "tri_state"))
      (node (ref "U2") (pin "8") (pinfunction "Q_8") (pintype "tri_state"))
      (node (ref "U6") (pin "8") (pinfunction "Q_8") (pintype "tri_state"))
      (node (ref "U9") (pin "8") (pinfunction "Q_8") (pintype "tri_state"))
    )
    (net (code "36") (name "/SDI2") (class "Default")
      (node (ref "U26") (pin "16") (pinfunction "SDO_16") (pintype "output"))
    )
    (net (code "37") (name "/SDO") (class "Default")
      (node (ref "U13") (pin "15") (pinfunction "D_15") (pintype "input"))
      (node (ref "U2") (pin "15") (pinfunction "D_15") (pintype "input"))
      (node (ref "U6") (pin "15") (pinfunction "D_15") (pintype "input"))
      (node (ref "U9") (pin "15") (pinfunction "D_15") (pintype "input"))
    )
    (net (code "38") (name "/SDO2") (class "Default")
      (node (ref "U26") (pin "15") (pinfunction "SDI_15") (pintype "input"))
    )
    (net (code "39") (name "/TXD") (class "Default")
      (node (ref "U15") (pin "11") (pinfunction "T1IN_11") (pintype "input"))
    )
    (net (code "40") (name "/TXD2") (class "Default")
      (node (ref "U16") (pin "25") (pinfunction "RXD_25") (pintype "input"))
    )
    (net (code "41") (name "/USB_RST") (class "Default")
      (node (ref "R82") (pin "1") (pinfunction "1_1") (pintype "passive"))
      (node (ref "U16") (pin "9") (pinfunction "~{RST}_9") (pintype "bidirectional"))
    )
    (net (code "42") (name "/VBAT") (class "Default")
      (node (ref "J19") (pin "1") (pinfunction "1_1") (pintype "passive"))
      (node (ref "U26") (pin "2") (pinfunction "VBAT_2") (pintype "power_in"))
    )
    (net (code "43") (name "/V_IN") (class "Default")
      (node (ref "R67") (pin "1") (pinfunction "1_1") (pintype "passive"))
    )
    (net (code "44") (name "/~{FORCEOFF}") (class "Default")
      (node (ref "U15") (pin "16") (pinfunction "~{FORCEOFF}_16") (pintype "input"))
    )
    (net (code "45") (name "/~{MEM0}") (class "Default")
      (node (ref "R4") (pin "1") (pinfunction "1_1") (pintype "passive"))
      (node (ref "U2") (pin "7") (pinfunction "~{S}_7") (pintype "input"))
    )
    (net (code "46") (name "/~{MEM1}") (class "Default")
      (node (ref "R16") (pin "1") (pinfunction "1_1") (pintype "passive"))
      (node (ref "U6") (pin "7") (pinfunction "~{S}_7") (pintype "input"))
    )
    (net (code "47") (name "/~{MEM2}") (class "Default")
      (node (ref "R31") (pin "1") (pinfunction "1_1") (pintype "passive"))
      (node (ref "U9") (pin "7") (pinfunction "~{S}_7") (pintype "input"))
    )
    (net (code "48") (name "/~{MEM3}") (class "Default")
      (node (ref "R58") (pin "1") (pinfunction "1_1") (pintype "passive"))
      (node (ref "U13") (pin "7") (pinfunction "~{S}_7") (pintype "input"))
    )
    (net (code "49") (name "/~{RS232_INVALID}") (class "Default")
      (node (ref "U15") (pin "10") (pinfunction "~{INVALID}_10") (pintype "output"))
    )
    (net (code "50") (name "GND") (class "Default")
      (node (ref "C12") (pin "2") (pinfunction "2_2") (pintype "passive"))
      (node (ref "C14") (pin "2") (pinfunction "2_2") (pintype "passive"))
      (node (ref "C16") (pin "2") (pinfunction "2_2") (pintype "passive"))
      (node (ref "C18") (pin "2") (pinfunction "2_2") (pintype "passive"))
      (node (ref "C19") (pin "2") (pinfunction "2_2") (pintype "passive"))
      (node (ref "C25") (pin "2") (pinfunction "2_2") (pintype "passive"))
      (node (ref "C27") (pin "2") (pinfunction "2_2") (pintype "passive"))
      (node (ref "C29") (pin "2") (pinfunction "2_2") (pintype "passive"))
      (node (ref "C33") (pin "2") (pinfunction "2_2") (pintype "passive"))
      (node (ref "C36") (pin "2") (pinfunction "2_2") (pintype "passive"))
      (node (ref "C38") (pin "2") (pinfunction "2_2") (pintype "passive"))
      (node (ref "C39") (pin "2") (pinfunction "2_2") (pintype "passive"))
      (node (ref "C40") (pin "2") (pinfunction "2_2") (pintype "passive"))
      (node (ref "C41") (pin "1") (pinfunction "1_1") (pintype "passive"))
      (node (ref "C42") (pin "2") (pinfunction "2_2") (pintype "passive"))
      (node (ref "C43") (pin "2") (pinfunction "2_2") (pintype "passive"))
      (node (ref "C45") (pin "2") (pinfunction "2_2") (pintype "passive"))
      (node (ref "C5") (pin "2") (pinfunction "2_2") (pintype "passive"))
      (node (ref "C54") (pin "2") (pinfunction "2_2") (pintype "passive"))
      (node (ref "C6") (pin "2") (pinfunction "2_2") (pintype "passive"))
      (node (ref "C7") (pin "2") (pinfunction "2_2") (pintype "passive"))
      (node (ref "D12") (pin "1") (pinfunction "A_1") (pintype "passive"))
      (node (ref "D13") (pin "1") (pinfunction "A_1") (pintype "passive"))
      (node (ref "D14") (pin "1") (pinfunction "A_1") (pintype "passive"))
      (node (ref "J14") (pin "4") (pinfunction "GND_4") (pintype "power_in"))
      (node (ref "J15") (pin "10") (pinfunction "MH1_10") (pintype "passive"))
      (node (ref "J15") (pin "11") (pinfunction "MH2_11") (pintype "passive"))
      (node (ref "J15") (pin "5") (pinfunction "5_5") (pintype "passive"))
      (node (ref "J18") (pin "1") (pinfunction "1_1") (pintype "passive"))
      (node (ref "J19") (pin "3") (pinfunction "3_3") (pintype "passive"))
      (node (ref "JP1") (pin "2") (pinfunction "2_2") (pintype "passive"))
      (node (ref "JP2") (pin "2") (pinfunction "2_2") (pintype "passive"))
      (node (ref "JP3") (pin "2") (pinfunction "2_2") (pintype "passive"))
      (node (ref "JP4") (pin "2") (pinfunction "2_2") (pintype "passive"))
      (node (ref "Q21") (pin "3") (pinfunction "S_3") (pintype "passive"))
      (node (ref "R28") (pin "1") (pinfunction "1_1") (pintype "passive"))
      (node (ref "R75") (pin "1") (pinfunction "CCW_1") (pintype "passive"))
      (node (ref "U11") (pin "7") (pinfunction "GND_7") (pintype "power_in"))
      (node (ref "U13") (pin "10") (pinfunction "VSS_10") (pintype "power_in"))
      (node (ref "U15") (pin "1") (pinfunction "~{EN}_1") (pintype "input"))
      (node (ref "U15") (pin "14") (pinfunction "GND_14") (pintype "power_in"))
      (node (ref "U16") (pin "3") (pinfunction "GND_3") (pintype "power_in"))
      (node (ref "U17") (pin "3") (pinfunction "GND_3") (pintype "power_in"))
      (node (ref "U2") (pin "10") (pinfunction "VSS_10") (pintype "power_in"))
      (node (ref "U26") (pin "1") (pinfunction "VCC2_1") (pintype "power_in"))
      (node (ref "U26") (pin "10") (pinfunction "GND_10") (pintype "power_in"))
      (node (ref "U4") (pin "8") (pinfunction "GND_8") (pintype "passive"))
      (node (ref "U6") (pin "10") (pinfunction "VSS_10") (pintype "power_in"))
      (node (ref "U9") (pin "10") (pinfunction "VSS_10") (pintype "power_in"))
    )
    (net (code "51") (name "Net-(C13-Pad2)") (class "Default")
      (node (ref "C13") (pin "2") (pinfunction "2_2") (pintype "passive"))
      (node (ref "R28") (pin "2") (pinfunction "2_2") (pintype "passive"))
      (node (ref "R30") (pin "1") (pinfunction "1_1") (pintype "passive"))
    )
    (net (code "52") (name "Net-(C19-Pad1)") (class "Default")
      (node (ref "C19") (pin "1") (pinfunction "1_1") (pintype "passive"))
      (node (ref "C21") (pin "1") (pinfunction "1_1") (pintype "passive"))
      (node (ref "R30") (pin "2") (pinfunction "2_2") (pintype "passive"))
    )
    (net (code "53") (name "Net-(C21-Pad2)") (class "Default")
      (node (ref "C21") (pin "2") (pinfunction "2_2") (pintype "passive"))
      (node (ref "R53") (pin "1") (pinfunction "1_1") (pintype "passive"))
    )
    (net (code "54") (name "Net-(D12-K)") (class "Default")
      (node (ref "D12") (pin "3") (pinfunction "K_3") (pintype "passive"))
      (node (ref "J14") (pin "1") (pinfunction "VBUS_1") (pintype "power_in"))
      (node (ref "U16") (pin "8") (pinfunction "VBUS_8") (pintype "input"))
    )
    (net (code "55") (name "Net-(D13-K)") (class "Default")
      (node (ref "D13") (pin "3") (pinfunction "K_3") (pintype "passive"))
      (node (ref "J14") (pin "2") (pinfunction "D-_2") (pintype "input"))
      (node (ref "U16") (pin "5") (pinfunction "D-_5") (pintype "bidirectional"))
    )
    (net (code "56") (name "Net-(D14-K)") (class "Default")
      (node (ref "D14") (pin "3") (pinfunction "K_3") (pintype "passive"))
      (node (ref "J14") (pin "3") (pinfunction "D+_3") (pintype "input"))
      (node (ref "U16") (pin "4") (pinfunction "D+_4") (pintype "bidirectional"))
    )
    (net (code "57") (name "Net-(J9-14GA_WIRE)") (class "Default")
      (node (ref "J9") (pin "1") (pinfunction "14GA_WIRE_1") (pintype "passive"))
      (node (ref "R59") (pin "2") (pinfunction "2_2") (pintype "passive"))
      (node (ref "U11") (pin "5") (pinfunction "VOUT1_5") (pintype "output"))
    )
    (net (code "58") (name "Net-(J10-14GA_WIRE)") (class "Default")
      (node (ref "J10") (pin "1") (pinfunction "14GA_WIRE_1") (pintype "passive"))
      (node (ref "U11") (pin "8") (pinfunction "VOUT2_8") (pintype "output"))
    )
    (net (code "59") (name "Net-(J18-Pad4)") (class "Default")
      (node (ref "J18") (pin "4") (pinfunction "4_4") (pintype "passive"))
      (node (ref "R76") (pin "2") (pinfunction "2_2") (pintype "passive"))
    )
    (net (code "60") (name "Net-(J18-Pad5)") (class "Default")
      (node (ref "J18") (pin "5") (pinfunction "5_5") (pintype "passive"))
      (node (ref "R77") (pin "2") (pinfunction "2_2") (pintype "passive"))
    )
    (net (code "61") (name "Net-(J18-Pad6)") (class "Default")
      (node (ref "J18") (pin "6") (pinfunction "6_6") (pintype "passive"))
      (node (ref "R78") (pin "2") (pinfunction "2_2") (pintype "passive"))
    )
    (net (code "62") (name "Net-(J18-Pad7)") (class "Default")
      (node (ref "J18") (pin "7") (pinfunction "7_7") (pintype "passive"))
      (node (ref "R20") (pin "2") (pinfunction "2_2") (pintype "passive"))
    )
    (net (code "63") (name "Net-(J18-Pad8)") (class "Default")
      (node (ref "J18") (pin "8") (pinfunction "8_8") (pintype "passive"))
      (node (ref "R21") (pin "2") (pinfunction "2_2") (pintype "passive"))
    )
    (net (code "64") (name "Net-(J18-Pad9)") (class "Default")
      (node (ref "J18") (pin "9") (pinfunction "9_9") (pintype "passive"))
      (node (ref "R22") (pin "2") (pinfunction "2_2") (pintype "passive"))
    )
    (net (code "65") (name "Net-(J18-Pad10)") (class "Default")
      (node (ref "J18") (pin "10") (pinfunction "10_10") (pintype "passive"))
      (node (ref "R23") (pin "2") (pinfunction "2_2") (pintype "passive"))
    )
    (net (code "66") (name "Net-(J18-Pad11)") (class "Default")
      (node (ref "J18") (pin "11") (pinfunction "11_11") (pintype "passive"))
      (node (ref "R24") (pin "2") (pinfunction "2_2") (pintype "passive"))
    )
    (net (code "67") (name "Net-(J18-Pad12)") (class "Default")
      (node (ref "J18") (pin "12") (pinfunction "12_12") (pintype "passive"))
      (node (ref "R25") (pin "2") (pinfunction "2_2") (pintype "passive"))
    )
    (net (code "68") (name "Net-(J18-Pad13)") (class "Default")
      (node (ref "J18") (pin "13") (pinfunction "13_13") (pintype "passive"))
      (node (ref "R26") (pin "2") (pinfunction "2_2") (pintype "passive"))
    )
    (net (code "69") (name "Net-(J18-Pad14)") (class "Default")
      (node (ref "J18") (pin "14") (pinfunction "14_14") (pintype "passive"))
      (node (ref "R27") (pin "2") (pinfunction "2_2") (pintype "passive"))
    )
    (net (code "70") (name "Net-(J18-Pad15)") (class "Default")
      (node (ref "J18") (pin "15") (pinfunction "15_15") (pintype "passive"))
      (node (ref "R79") (pin "2") (pinfunction "2_2") (pintype "passive"))
    )
    (net (code "71") (name "Net-(J18-Pad16)") (class "Default")
      (node (ref "J18") (pin "16") (pinfunction "16_16") (pintype "passive"))
      (node (ref "R80") (pin "2") (pinfunction "2_2") (pintype "passive"))
    )
    (net (code "72") (name "Net-(J18-Pad17)") (class "Default")
      (node (ref "J18") (pin "17") (pinfunction "17_17") (pintype "passive"))
      (node (ref "R81") (pin "2") (pinfunction "2_2") (pintype "passive"))
    )
    (net (code "73") (name "Net-(J18-Pad19)") (class "Default")
      (node (ref "J18") (pin "19") (pinfunction "19_19") (pintype "passive"))
      (node (ref "R67") (pin "2") (pinfunction "2_2") (pintype "passive"))
    )
    (net (code "74") (name "Net-(Q21-D)") (class "Default")
      (node (ref "J18") (pin "20") (pinfunction "20_20") (pintype "passive"))
      (node (ref "Q21") (pin "2") (pinfunction "D_2") (pintype "passive"))
    )
    (net (code "75") (name "Net-(Q21-G)") (class "Default")
      (node (ref "Q21") (pin "1") (pinfunction "G_1") (pintype "passive"))
      (node (ref "R83") (pin "2") (pinfunction "2_2") (pintype "passive"))
    )
    (net (code "76") (name "Net-(R75-CW)") (class "Default")
      (node (ref "C41") (pin "2") (pinfunction "2_2") (pintype "passive"))
      (node (ref "R75") (pin "3") (pinfunction "CW_3") (pintype "passive"))
      (node (ref "U17") (pin "5") (pinfunction "VOUT_5") (pintype "output"))
    )
    (net (code "77") (name "Net-(R75-T)") (class "Default")
      (node (ref "J18") (pin "3") (pinfunction "3_3") (pintype "passive"))
      (node (ref "R75") (pin "2") (pinfunction "T_2") (pintype "passive"))
    )
    (net (code "78") (name "Net-(U4-AOUTR)") (class "Default")
      (node (ref "C13") (pin "1") (pinfunction "1_1") (pintype "passive"))
      (node (ref "U4") (pin "10") (pinfunction "AOUTR_10") (pintype "passive"))
    )
    (net (code "79") (name "Net-(U4-FILT+)") (class "Default")
      (node (ref "C12") (pin "1") (pinfunction "1_1") (pintype "passive"))
      (node (ref "U4") (pin "6") (pinfunction "FILT+_6") (pintype "passive"))
    )
    (net (code "80") (name "Net-(U4-VQ)") (class "Default")
      (node (ref "C5") (pin "1") (pinfunction "1_1") (pintype "passive"))
      (node (ref "C7") (pin "1") (pinfunction "1_1") (pintype "passive"))
      (node (ref "U4") (pin "5") (pinfunction "VQ_5") (pintype "passive"))
    )
    (net (code "81") (name "Net-(U11-BYP)") (class "Default")
      (node (ref "C27") (pin "1") (pinfunction "1_1") (pintype "passive"))
      (node (ref "U11") (pin "2") (pinfunction "BYP_2") (pintype "passive"))
      (node (ref "U11") (pin "3") (pinfunction "IN+_3") (pintype "input"))
    )
    (net (code "82") (name "Net-(U11-IN-)") (class "Default")
      (node (ref "R53") (pin "2") (pinfunction "2_2") (pintype "passive"))
      (node (ref "R59") (pin "1") (pinfunction "1_1") (pintype "passive"))
      (node (ref "U11") (pin "4") (pinfunction "IN-_4") (pintype "input"))
    )
    (net (code "83") (name "Net-(U13-~{HOLD})") (class "Default")
      (node (ref "R2") (pin "2") (pinfunction "2_2") (pintype "passive"))
      (node (ref "U13") (pin "1") (pinfunction "~{HOLD}_1") (pintype "input"))
      (node (ref "U2") (pin "1") (pinfunction "~{HOLD}_1") (pintype "input"))
      (node (ref "U6") (pin "1") (pinfunction "~{HOLD}_1") (pintype "input"))
      (node (ref "U9") (pin "1") (pinfunction "~{HOLD}_1") (pintype "input"))
    )
    (net (code "84") (name "Net-(U15-C1+)") (class "Default")
      (node (ref "C34") (pin "1") (pinfunction "1_1") (pintype "passive"))
      (node (ref "U15") (pin "2") (pinfunction "C1+_2") (pintype "passive"))
    )
    (net (code "85") (name "Net-(U15-C1-)") (class "Default")
      (node (ref "C34") (pin "2") (pinfunction "2_2") (pintype "passive"))
      (node (ref "U15") (pin "4") (pinfunction "C1-_4") (pintype "passive"))
    )
    (net (code "86") (name "Net-(U15-C2+)") (class "Default")
      (node (ref "C35") (pin "1") (pinfunction "1_1") (pintype "passive"))
      (node (ref "U15") (pin "5") (pinfunction "C2+_5") (pintype "passive"))
    )
    (net (code "87") (name "Net-(U15-C2-)") (class "Default")
      (node (ref "C35") (pin "2") (pinfunction "2_2") (pintype "passive"))
      (node (ref "U15") (pin "6") (pinfunction "C2-_6") (pintype "passive"))
    )
    (net (code "88") (name "Net-(U15-R1IN)") (class "Default")
      (node (ref "J15") (pin "3") (pinfunction "3_3") (pintype "passive"))
      (node (ref "U15") (pin "8") (pinfunction "R1IN_8") (pintype "input"))
    )
    (net (code "89") (name "Net-(U15-T1OUT)") (class "Default")
      (node (ref "J15") (pin "2") (pinfunction "2_2") (pintype "passive"))
      (node (ref "U15") (pin "13") (pinfunction "T1OUT_13") (pintype "output"))
    )
    (net (code "90") (name "Net-(U15-V+)") (class "Default")
      (node (ref "C38") (pin "1") (pinfunction "1_1") (pintype "passive"))
      (node (ref "U15") (pin "3") (pinfunction "V+_3") (pintype "power_in"))
    )
    (net (code "91") (name "Net-(U15-V-)") (class "Default")
      (node (ref "C40") (pin "1") (pinfunction "1_1") (pintype "passive"))
      (node (ref "U15") (pin "7") (pinfunction "V-_7") (pintype "power_in"))
    )
    (net (code "92") (name "Net-(U17-CAP+)") (class "Default")
      (node (ref "C44") (pin "1") (pinfunction "1_1") (pintype "passive"))
      (node (ref "U17") (pin "2") (pinfunction "CAP+_2") (pintype "passive"))
    )
    (net (code "93") (name "Net-(U17-CAP-)") (class "Default")
      (node (ref "C44") (pin "2") (pinfunction "2_2") (pintype "passive"))
      (node (ref "U17") (pin "4") (pinfunction "CAP-_4") (pintype "passive"))
    )
    (net (code "94") (name "Net-(U26-X1)") (class "Default")
      (node (ref "U26") (pin "3") (pinfunction "X1_3") (pintype "input"))
      (node (ref "Y2") (pin "1") (pinfunction "OSC1_1") (pintype "passive"))
    )
    (net (code "95") (name "Net-(U26-X2)") (class "Default")
      (node (ref "U26") (pin "5") (pinfunction "X2_5") (pintype "input"))
      (node (ref "Y2") (pin "4") (pinfunction "OSC2_4") (pintype "passive"))
    )
    (net (code "96") (name "VCC") (class "Default")
      (node (ref "C14") (pin "1") (pinfunction "1_1") (pintype "passive"))
      (node (ref "C16") (pin "1") (pinfunction "1_1") (pintype "passive"))
      (node (ref "C18") (pin "1") (pinfunction "1_1") (pintype "passive"))
      (node (ref "C25") (pin "1") (pinfunction "1_1") (pintype "passive"))
      (node (ref "C33") (pin "1") (pinfunction "1_1") (pintype "passive"))
      (node (ref "C36") (pin "1") (pinfunction "1_1") (pintype "passive"))
      (node (ref "C39") (pin "1") (pinfunction "1_1") (pintype "passive"))
      (node (ref "C54") (pin "1") (pinfunction "1_1") (pintype "passive"))
      (node (ref "C6") (pin "1") (pinfunction "1_1") (pintype "passive"))
      (node (ref "R1") (pin "1") (pinfunction "1_1") (pintype "passive"))
      (node (ref "R16") (pin "2") (pinfunction "2_2") (pintype "passive"))
      (node (ref "R2") (pin "1") (pinfunction "1_1") (pintype "passive"))
      (node (ref "R31") (pin "2") (pinfunction "2_2") (pintype "passive"))
      (node (ref "R4") (pin "2") (pinfunction "2_2") (pintype "passive"))
      (node (ref "R54") (pin "2") (pinfunction "2_2") (pintype "passive"))
      (node (ref "R58") (pin "2") (pinfunction "2_2") (pintype "passive"))
      (node (ref "R60") (pin "2") (pinfunction "2_2") (pintype "passive"))
      (node (ref "R61") (pin "2") (pinfunction "2_2") (pintype "passive"))
      (node (ref "R68") (pin "2") (pinfunction "2_2") (pintype "passive"))
      (node (ref "R74") (pin "2") (pinfunction "2_2") (pintype "passive"))
      (node (ref "R82") (pin "2") (pinfunction "2_2") (pintype "passive"))
      (node (ref "U13") (pin "2") (pinfunction "VCC_2") (pintype "power_in"))
      (node (ref "U15") (pin "15") (pinfunction "VCC_15") (pintype "power_in"))
      (node (ref "U16") (pin "6") (pinfunction "VDD_6") (pintype "power_in"))
      (node (ref "U16") (pin "7") (pinfunction "REGIN_7") (pintype "input"))
      (node (ref "U2") (pin "2") (pinfunction "VCC_2") (pintype "power_in"))
      (node (ref "U26") (pin "11") (pinfunction "SERMODE_11") (pintype "input"))
      (node (ref "U26") (pin "17") (pinfunction "VCCIF_17") (pintype "power_in"))
      (node (ref "U26") (pin "20") (pinfunction "VCC1_20") (pintype "power_in"))
      (node (ref "U4") (pin "9") (pinfunction "VA_9") (pintype "passive"))
      (node (ref "U6") (pin "2") (pinfunction "VCC_2") (pintype "power_in"))
      (node (ref "U9") (pin "2") (pinfunction "VCC_2") (pintype "power_in"))
    )
    (net (code "97") (name "unconnected-(J14-SHLD-Pad5)") (class "Default")
      (node (ref "J14") (pin "5") (pinfunction "SHLD_5") (pintype "passive"))
    )
    (net (code "98") (name "unconnected-(J14-SHLD-Pad6)") (class "Default")
      (node (ref "J14") (pin "6") (pinfunction "SHLD_6") (pintype "passive"))
    )
    (net (code "99") (name "unconnected-(J15-Pad1)") (class "Default")
      (node (ref "J15") (pin "1") (pinfunction "1_1") (pintype "passive"))
    )
    (net (code "100") (name "unconnected-(J15-Pad4)") (class "Default")
      (node (ref "J15") (pin "4") (pinfunction "4_4") (pintype "passive"))
    )
    (net (code "101") (name "unconnected-(J15-Pad6)") (class "Default")
      (node (ref "J15") (pin "6") (pinfunction "6_6") (pintype "passive"))
    )
    (net (code "102") (name "unconnected-(J15-Pad7)") (class "Default")
      (node (ref "J15") (pin "7") (pinfunction "7_7") (pintype "passive"))
    )
    (net (code "103") (name "unconnected-(J15-Pad8)") (class "Default")
      (node (ref "J15") (pin "8") (pinfunction "8_8") (pintype "passive"))
    )
    (net (code "104") (name "unconnected-(J15-Pad9)") (class "Default")
      (node (ref "J15") (pin "9") (pinfunction "9_9") (pintype "passive"))
    )
    (net (code "105") (name "unconnected-(J18-Pad18)") (class "Default")
      (node (ref "J18") (pin "18") (pinfunction "18_18") (pintype "passive"))
    )
    (net (code "106") (name "unconnected-(J19-Pad2)") (class "Default")
      (node (ref "J19") (pin "2") (pinfunction "2_2") (pintype "passive"))
    )
    (net (code "107") (name "unconnected-(J19-Pad5)") (class "Default")
      (node (ref "J19") (pin "5") (pinfunction "5_5") (pintype "passive"))
    )
    (net (code "108") (name "unconnected-(U4-AOUTL-Pad7)") (class "Default")
      (node (ref "U4") (pin "7") (pinfunction "AOUTL_7") (pintype "passive"))
    )
    (net (code "109") (name "unconnected-(U16-CTS-Pad23)") (class "Default")
      (node (ref "U16") (pin "23") (pinfunction "CTS_23") (pintype "input"))
    )
    (net (code "110") (name "unconnected-(U16-DCD-Pad1)") (class "Default")
      (node (ref "U16") (pin "1") (pinfunction "DCD_1") (pintype "input"))
    )
    (net (code "111") (name "unconnected-(U16-DSR-Pad27)") (class "Default")
      (node (ref "U16") (pin "27") (pinfunction "DSR_27") (pintype "input"))
    )
    (net (code "112") (name "unconnected-(U16-DTR-Pad28)") (class "Default")
      (node (ref "U16") (pin "28") (pinfunction "DTR_28") (pintype "output"))
    )
    (net (code "113") (name "unconnected-(U16-RI-Pad2)") (class "Default")
      (node (ref "U16") (pin "2") (pinfunction "RI_2") (pintype "input"))
    )
    (net (code "114") (name "unconnected-(U16-RTS-Pad24)") (class "Default")
      (node (ref "U16") (pin "24") (pinfunction "RTS_24") (pintype "output"))
    )
    (net (code "115") (name "unconnected-(U16-SUSPEND-Pad12)") (class "Default")
      (node (ref "U16") (pin "12") (pinfunction "SUSPEND_12") (pintype "output"))
    )
    (net (code "116") (name "unconnected-(U16-~{SUSPEND}-Pad11)") (class "Default")
      (node (ref "U16") (pin "11") (pinfunction "~{SUSPEND}_11") (pintype "output"))
    )
    (net (code "117") (name "unconnected-(U17-BOOST-Pad1)") (class "Default")
      (node (ref "U17") (pin "1") (pinfunction "BOOST_1") (pintype "passive"))
    )
    (net (code "118") (name "unconnected-(U17-LV-Pad6)") (class "Default")
      (node (ref "U17") (pin "6") (pinfunction "LV_6") (pintype "passive"))
    )
    (net (code "119") (name "unconnected-(U17-OSC-Pad7)") (class "Default")
      (node (ref "U17") (pin "7") (pinfunction "OSC_7") (pintype "input"))
    )
    (net (code "120") (name "unconnected-(U26-1Hz-Pad9)") (class "Default")
      (node (ref "U26") (pin "9") (pinfunction "1Hz_9") (pintype "output"))
    )
    (net (code "121") (name "unconnected-(U26-32KHz-Pad18)") (class "Default")
      (node (ref "U26") (pin "18") (pinfunction "32KHz_18") (pintype "output"))
    )
    (net (code "122") (name "unconnected-(U26-NC-Pad4)") (class "Default")
      (node (ref "U26") (pin "4") (pinfunction "NC_4") (pintype "passive"))
    )
    (net (code "123") (name "unconnected-(U26-NC-Pad6)") (class "Default")
      (node (ref "U26") (pin "6") (pinfunction "NC_6") (pintype "passive"))
    )
    (net (code "124") (name "unconnected-(U26-NC-Pad13)") (class "Default")
      (node (ref "U26") (pin "13") (pinfunction "NC_13") (pintype "passive"))
    )
    (net (code "125") (name "unconnected-(U26-NC-Pad19)") (class "Default")
      (node (ref "U26") (pin "19") (pinfunction "NC_19") (pintype "passive"))
    )
    (net (code "126") (name "unconnected-(U26-~{INT0}-Pad7)") (class "Default")
      (node (ref "U26") (pin "7") (pinfunction "~{INT0}_7") (pintype "output"))
    )
    (net (code "127") (name "unconnected-(U26-~{INT1}-Pad8)") (class "Default")
      (node (ref "U26") (pin "8") (pinfunction "~{INT1}_8") (pintype "output"))
    )
    (net (code "128") (name "unconnected-(Y2-COM-Pad2)") (class "Default")
      (node (ref "Y2") (pin "2") (pinfunction "COM_2") (pintype "passive"))
    )
    (net (code "129") (name "unconnected-(Y2-COM-Pad3)") (class "Default")
      (node (ref "Y2") (pin "3") (pinfunction "COM_3") (pintype "passive"))
    )
  )
)
